# 11_LMS1_Power.net
KiCad netlist of a schematic drawn in Altium Designer
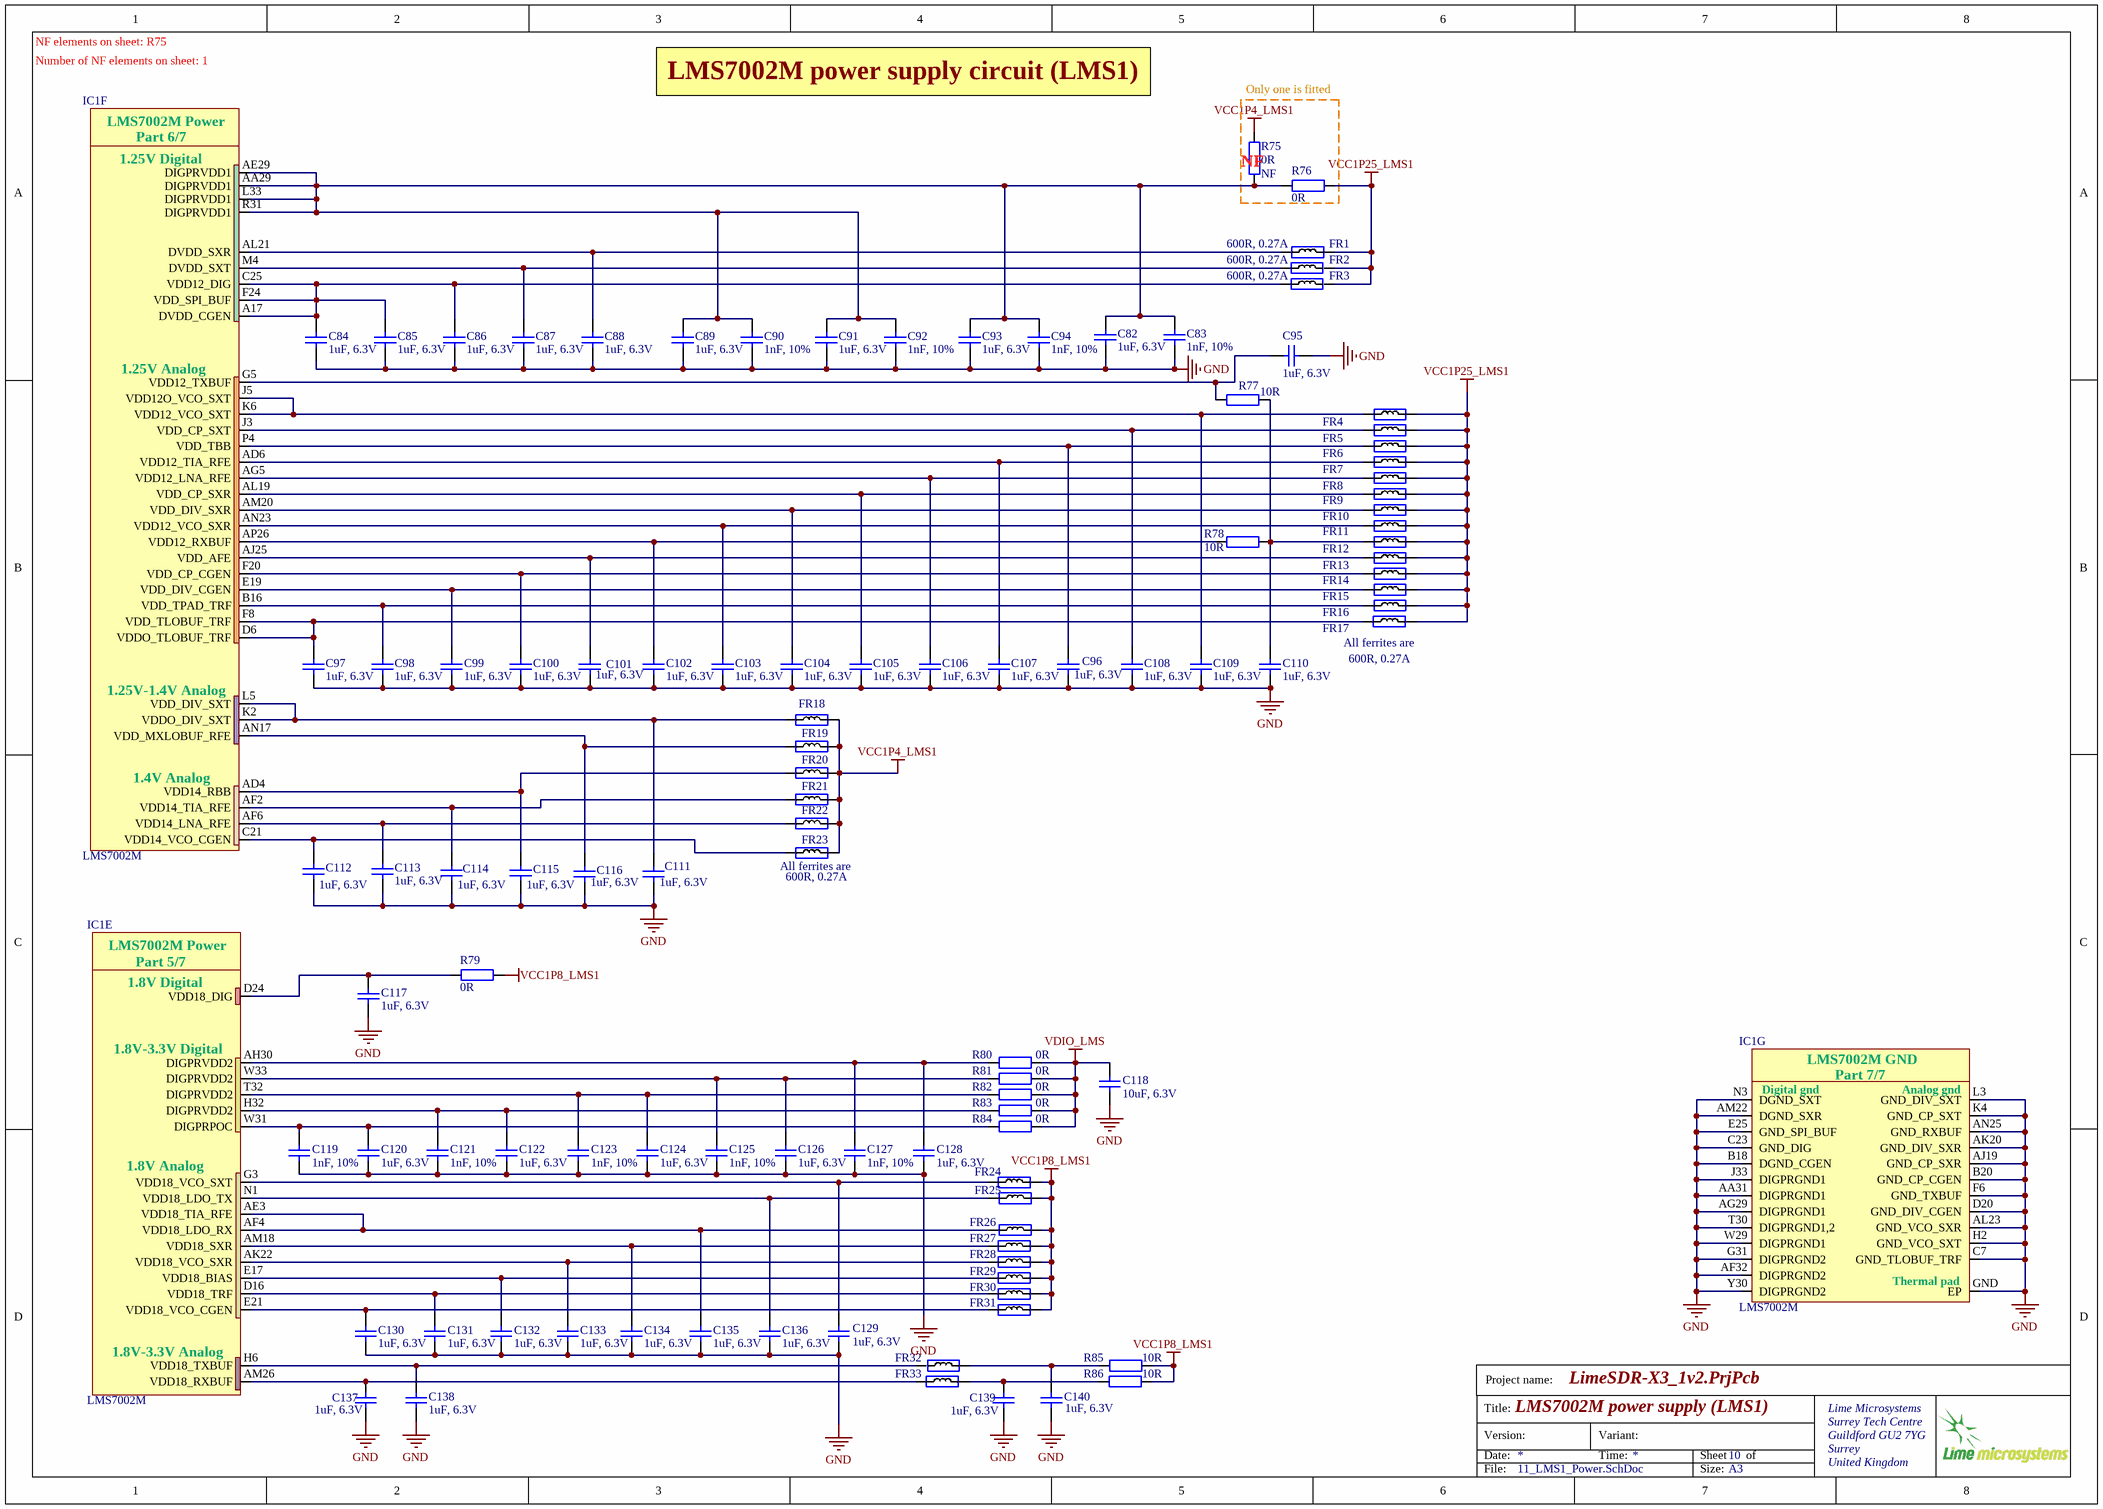
[diagram p0: 11_LMS1_Power.SchDoc]

(export (version "E")
  (design (tool "Eeschema 10.0.6"))
  (components
    (comp (ref "C82")
      (value "1uF, 6.3V")
      (footprint "CAP0201")
      (fields (field (name "TOLERANCE") "±20%") (field (name "MANUFACTURER") "TDK Corporation"))
      (libsource (lib "") (part "Cap_0402_1"))
    )
    (comp (ref "C83")
      (value "1nF, 10%")
      (footprint "CAP0201")
      (fields (field (name "TOLERANCE") "±10%") (field (name "MANUFACTURER") "TDK Corporation"))
      (libsource (lib "") (part "Cap_0402_1"))
    )
    (comp (ref "C84")
      (value "1uF, 6.3V")
      (footprint "CAP0201")
      (fields (field (name "TOLERANCE") "±20%") (field (name "MANUFACTURER") "TDK Corporation"))
      (libsource (lib "") (part "Cap_0402_3"))
    )
    (comp (ref "C85")
      (value "1uF, 6.3V")
      (footprint "CAP0201")
      (fields (field (name "TOLERANCE") "±20%") (field (name "MANUFACTURER") "TDK Corporation"))
      (libsource (lib "") (part "Cap_0402_3"))
    )
    (comp (ref "C86")
      (value "1uF, 6.3V")
      (footprint "CAP0201")
      (fields (field (name "TOLERANCE") "±20%") (field (name "MANUFACTURER") "TDK Corporation"))
      (libsource (lib "") (part "Cap_0402_3"))
    )
    (comp (ref "C87")
      (value "1uF, 6.3V")
      (footprint "CAP0201")
      (fields (field (name "TOLERANCE") "±20%") (field (name "MANUFACTURER") "TDK Corporation"))
      (libsource (lib "") (part "Cap_0402_1"))
    )
    (comp (ref "C88")
      (value "1uF, 6.3V")
      (footprint "CAP0201")
      (fields (field (name "TOLERANCE") "±20%") (field (name "MANUFACTURER") "TDK Corporation"))
      (libsource (lib "") (part "Cap_0402_3"))
    )
    (comp (ref "C89")
      (value "1uF, 6.3V")
      (footprint "CAP0201")
      (fields (field (name "TOLERANCE") "±20%") (field (name "MANUFACTURER") "TDK Corporation"))
      (libsource (lib "") (part "Cap_0402_1"))
    )
    (comp (ref "C90")
      (value "1nF, 10%")
      (footprint "CAP0201")
      (fields (field (name "TOLERANCE") "±10%") (field (name "MANUFACTURER") "TDK Corporation"))
      (libsource (lib "") (part "Cap_0402_1"))
    )
    (comp (ref "C91")
      (value "1uF, 6.3V")
      (footprint "CAP0201")
      (fields (field (name "TOLERANCE") "±20%") (field (name "MANUFACTURER") "TDK Corporation"))
      (libsource (lib "") (part "Cap_0402_1"))
    )
    (comp (ref "C92")
      (value "1nF, 10%")
      (footprint "CAP0201")
      (fields (field (name "TOLERANCE") "±10%") (field (name "MANUFACTURER") "TDK Corporation"))
      (libsource (lib "") (part "Cap_0402_1"))
    )
    (comp (ref "C93")
      (value "1uF, 6.3V")
      (footprint "CAP0201")
      (fields (field (name "TOLERANCE") "±20%") (field (name "MANUFACTURER") "TDK Corporation"))
      (libsource (lib "") (part "Cap_0402_1"))
    )
    (comp (ref "C94")
      (value "1nF, 10%")
      (footprint "CAP0201")
      (fields (field (name "TOLERANCE") "±10%") (field (name "MANUFACTURER") "TDK Corporation"))
      (libsource (lib "") (part "Cap_0402_1"))
    )
    (comp (ref "C95")
      (value "1uF, 6.3V")
      (footprint "CAP0201")
      (fields (field (name "TOLERANCE") "±20%") (field (name "MANUFACTURER") "TDK Corporation"))
      (libsource (lib "") (part "Cap_0402_4"))
    )
    (comp (ref "C96")
      (value "1uF, 6.3V")
      (footprint "CAP0201")
      (fields (field (name "TOLERANCE") "±20%") (field (name "MANUFACTURER") "TDK Corporation"))
      (libsource (lib "") (part "Cap_0402_3"))
    )
    (comp (ref "C97")
      (value "1uF, 6.3V")
      (footprint "CAP0201")
      (fields (field (name "TOLERANCE") "±20%") (field (name "MANUFACTURER") "TDK Corporation"))
      (libsource (lib "") (part "Cap_0402_3"))
    )
    (comp (ref "C98")
      (value "1uF, 6.3V")
      (footprint "CAP0201")
      (fields (field (name "TOLERANCE") "±20%") (field (name "MANUFACTURER") "TDK Corporation"))
      (libsource (lib "") (part "Cap_0402_3"))
    )
    (comp (ref "C99")
      (value "1uF, 6.3V")
      (footprint "CAP0201")
      (fields (field (name "TOLERANCE") "±20%") (field (name "MANUFACTURER") "TDK Corporation"))
      (libsource (lib "") (part "Cap_0402_3"))
    )
    (comp (ref "C100")
      (value "1uF, 6.3V")
      (footprint "CAP0201")
      (fields (field (name "TOLERANCE") "±20%") (field (name "MANUFACTURER") "TDK Corporation"))
      (libsource (lib "") (part "Cap_0402_1"))
    )
    (comp (ref "C101")
      (value "1uF, 6.3V")
      (footprint "CAP0201")
      (fields (field (name "TOLERANCE") "±20%") (field (name "MANUFACTURER") "TDK Corporation"))
      (libsource (lib "") (part "Cap_0402_3"))
    )
    (comp (ref "C102")
      (value "1uF, 6.3V")
      (footprint "CAP0201")
      (fields (field (name "TOLERANCE") "±20%") (field (name "MANUFACTURER") "TDK Corporation"))
      (libsource (lib "") (part "Cap_0402_3"))
    )
    (comp (ref "C103")
      (value "1uF, 6.3V")
      (footprint "CAP0201")
      (fields (field (name "TOLERANCE") "±20%") (field (name "MANUFACTURER") "TDK Corporation"))
      (libsource (lib "") (part "Cap_0402_3"))
    )
    (comp (ref "C104")
      (value "1uF, 6.3V")
      (footprint "CAP0201")
      (fields (field (name "TOLERANCE") "±20%") (field (name "MANUFACTURER") "TDK Corporation"))
      (libsource (lib "") (part "Cap_0402_3"))
    )
    (comp (ref "C105")
      (value "1uF, 6.3V")
      (footprint "CAP0201")
      (fields (field (name "TOLERANCE") "±20%") (field (name "MANUFACTURER") "TDK Corporation"))
      (libsource (lib "") (part "Cap_0402_3"))
    )
    (comp (ref "C106")
      (value "1uF, 6.3V")
      (footprint "CAP0201")
      (fields (field (name "TOLERANCE") "±20%") (field (name "MANUFACTURER") "TDK Corporation"))
      (libsource (lib "") (part "Cap_0402_3"))
    )
    (comp (ref "C107")
      (value "1uF, 6.3V")
      (footprint "CAP0201")
      (fields (field (name "TOLERANCE") "±20%") (field (name "MANUFACTURER") "TDK Corporation"))
      (libsource (lib "") (part "Cap_0402_1"))
    )
    (comp (ref "C108")
      (value "1uF, 6.3V")
      (footprint "CAP0201")
      (fields (field (name "TOLERANCE") "±20%") (field (name "MANUFACTURER") "TDK Corporation"))
      (libsource (lib "") (part "Cap_0402_3"))
    )
    (comp (ref "C109")
      (value "1uF, 6.3V")
      (footprint "CAP0201")
      (fields (field (name "TOLERANCE") "±20%") (field (name "MANUFACTURER") "TDK Corporation"))
      (libsource (lib "") (part "Cap_0402_1"))
    )
    (comp (ref "C110")
      (value "1uF, 6.3V")
      (footprint "CAP0201")
      (fields (field (name "TOLERANCE") "±20%") (field (name "MANUFACTURER") "TDK Corporation"))
      (libsource (lib "") (part "Cap_0402_1"))
    )
    (comp (ref "C111")
      (value "1uF, 6.3V")
      (footprint "CAP0201")
      (fields (field (name "TOLERANCE") "±20%") (field (name "MANUFACTURER") "TDK Corporation"))
      (libsource (lib "") (part "Cap_0402_3"))
    )
    (comp (ref "C112")
      (value "1uF, 6.3V")
      (footprint "CAP0201")
      (fields (field (name "TOLERANCE") "±20%") (field (name "MANUFACTURER") "TDK Corporation"))
      (libsource (lib "") (part "Cap_0402_3"))
    )
    (comp (ref "C113")
      (value "1uF, 6.3V")
      (footprint "CAP0201")
      (fields (field (name "TOLERANCE") "±20%") (field (name "MANUFACTURER") "TDK Corporation"))
      (libsource (lib "") (part "Cap_0402_3"))
    )
    (comp (ref "C114")
      (value "1uF, 6.3V")
      (footprint "CAP0201")
      (fields (field (name "TOLERANCE") "±20%") (field (name "MANUFACTURER") "TDK Corporation"))
      (libsource (lib "LimeMicroAltiumLib_schLib") (part "Cap_0402"))
    )
    (comp (ref "C115")
      (value "1uF, 6.3V")
      (footprint "CAP0201")
      (fields (field (name "TOLERANCE") "±20%") (field (name "MANUFACTURER") "TDK Corporation"))
      (libsource (lib "LimeMicroAltiumLib_schLib") (part "Cap_0402"))
    )
    (comp (ref "C116")
      (value "1uF, 6.3V")
      (footprint "CAP0201")
      (fields (field (name "TOLERANCE") "±20%") (field (name "MANUFACTURER") "TDK Corporation"))
      (libsource (lib "") (part "Cap_0402_3"))
    )
    (comp (ref "C117")
      (value "1uF, 6.3V")
      (footprint "CAP0201")
      (fields (field (name "TOLERANCE") "±20%") (field (name "MANUFACTURER") "TDK Corporation"))
      (libsource (lib "") (part "Cap_0402_2"))
    )
    (comp (ref "C118")
      (value "10uF, 6.3V")
      (footprint "CAP0603")
      (fields (field (name "TOLERANCE") "±20%") (field (name "MANUFACTURER") "Yageo"))
      (libsource (lib "LimeFPGAboard_schLib") (part "Cap_0603"))
    )
    (comp (ref "C119")
      (value "1nF, 10%")
      (footprint "CAP0201")
      (fields (field (name "TOLERANCE") "±10%") (field (name "MANUFACTURER") "TDK Corporation"))
      (libsource (lib "") (part "Cap_0402_2"))
    )
    (comp (ref "C120")
      (value "1uF, 6.3V")
      (footprint "CAP0201")
      (fields (field (name "TOLERANCE") "±20%") (field (name "MANUFACTURER") "TDK Corporation"))
      (libsource (lib "") (part "Cap_0402_2"))
    )
    (comp (ref "C121")
      (value "1nF, 10%")
      (footprint "CAP0201")
      (fields (field (name "TOLERANCE") "±10%") (field (name "MANUFACTURER") "TDK Corporation"))
      (libsource (lib "") (part "Cap_0402_2"))
    )
    (comp (ref "C122")
      (value "1uF, 6.3V")
      (footprint "CAP0201")
      (fields (field (name "TOLERANCE") "±20%") (field (name "MANUFACTURER") "TDK Corporation"))
      (libsource (lib "") (part "Cap_0402_2"))
    )
    (comp (ref "C123")
      (value "1nF, 10%")
      (footprint "CAP0201")
      (fields (field (name "TOLERANCE") "±10%") (field (name "MANUFACTURER") "TDK Corporation"))
      (libsource (lib "") (part "Cap_0402_2"))
    )
    (comp (ref "C124")
      (value "1uF, 6.3V")
      (footprint "CAP0201")
      (fields (field (name "TOLERANCE") "±20%") (field (name "MANUFACTURER") "TDK Corporation"))
      (libsource (lib "") (part "Cap_0402_2"))
    )
    (comp (ref "C125")
      (value "1nF, 10%")
      (footprint "CAP0201")
      (fields (field (name "TOLERANCE") "±10%") (field (name "MANUFACTURER") "TDK Corporation"))
      (libsource (lib "") (part "Cap_0402_2"))
    )
    (comp (ref "C126")
      (value "1uF, 6.3V")
      (footprint "CAP0201")
      (fields (field (name "TOLERANCE") "±20%") (field (name "MANUFACTURER") "TDK Corporation"))
      (libsource (lib "") (part "Cap_0402_2"))
    )
    (comp (ref "C127")
      (value "1nF, 10%")
      (footprint "CAP0201")
      (fields (field (name "TOLERANCE") "±10%") (field (name "MANUFACTURER") "TDK Corporation"))
      (libsource (lib "") (part "Cap_0402_2"))
    )
    (comp (ref "C128")
      (value "1uF, 6.3V")
      (footprint "CAP0201")
      (fields (field (name "TOLERANCE") "±20%") (field (name "MANUFACTURER") "TDK Corporation"))
      (libsource (lib "") (part "Cap_0402_2"))
    )
    (comp (ref "C129")
      (value "1uF, 6.3V")
      (footprint "CAP0201")
      (fields (field (name "TOLERANCE") "±20%") (field (name "MANUFACTURER") "TDK Corporation"))
      (libsource (lib "") (part "Cap_0402_2"))
    )
    (comp (ref "C130")
      (value "1uF, 6.3V")
      (footprint "CAP0201")
      (fields (field (name "TOLERANCE") "±20%") (field (name "MANUFACTURER") "TDK Corporation"))
      (libsource (lib "") (part "Cap_0402_2"))
    )
    (comp (ref "C131")
      (value "1uF, 6.3V")
      (footprint "CAP0201")
      (fields (field (name "TOLERANCE") "±20%") (field (name "MANUFACTURER") "TDK Corporation"))
      (libsource (lib "") (part "Cap_0402_2"))
    )
    (comp (ref "C132")
      (value "1uF, 6.3V")
      (footprint "CAP0201")
      (fields (field (name "TOLERANCE") "±20%") (field (name "MANUFACTURER") "TDK Corporation"))
      (libsource (lib "") (part "Cap_0402_2"))
    )
    (comp (ref "C133")
      (value "1uF, 6.3V")
      (footprint "CAP0201")
      (fields (field (name "TOLERANCE") "±20%") (field (name "MANUFACTURER") "TDK Corporation"))
      (libsource (lib "") (part "Cap_0402_2"))
    )
    (comp (ref "C134")
      (value "1uF, 6.3V")
      (footprint "CAP0201")
      (fields (field (name "TOLERANCE") "±20%") (field (name "MANUFACTURER") "TDK Corporation"))
      (libsource (lib "") (part "Cap_0402_2"))
    )
    (comp (ref "C135")
      (value "1uF, 6.3V")
      (footprint "CAP0201")
      (fields (field (name "TOLERANCE") "±20%") (field (name "MANUFACTURER") "TDK Corporation"))
      (libsource (lib "") (part "Cap_0402_2"))
    )
    (comp (ref "C136")
      (value "1uF, 6.3V")
      (footprint "CAP0201")
      (fields (field (name "TOLERANCE") "±20%") (field (name "MANUFACTURER") "TDK Corporation"))
      (libsource (lib "") (part "Cap_0402_2"))
    )
    (comp (ref "C137")
      (value "1uF, 6.3V")
      (footprint "CAP0201")
      (fields (field (name "TOLERANCE") "±20%") (field (name "MANUFACTURER") "TDK Corporation"))
      (libsource (lib "") (part "Cap_0402_2"))
    )
    (comp (ref "C138")
      (value "1uF, 6.3V")
      (footprint "CAP0201")
      (fields (field (name "TOLERANCE") "±20%") (field (name "MANUFACTURER") "TDK Corporation"))
      (libsource (lib "") (part "Cap_0402_2"))
    )
    (comp (ref "C139")
      (value "1uF, 6.3V")
      (footprint "CAP0201")
      (fields (field (name "TOLERANCE") "±20%") (field (name "MANUFACTURER") "TDK Corporation"))
      (libsource (lib "") (part "Cap_0402_2"))
    )
    (comp (ref "C140")
      (value "1uF, 6.3V")
      (footprint "CAP0201")
      (fields (field (name "TOLERANCE") "±20%") (field (name "MANUFACTURER") "TDK Corporation"))
      (libsource (lib "") (part "Cap_0402_2"))
    )
    (comp (ref "FR1")
      (value "600R, 0.27A")
      (footprint "RES0201")
      (fields (field (name "MANUFACTURER") "Taiyo Yuden"))
      (libsource (lib "") (part "Ferrite_2"))
    )
    (comp (ref "FR2")
      (value "600R, 0.27A")
      (footprint "RES0201")
      (fields (field (name "MANUFACTURER") "Taiyo Yuden"))
      (libsource (lib "LimeMicroAltiumLib_schLib") (part "Ferrite"))
    )
    (comp (ref "FR3")
      (value "600R, 0.27A")
      (footprint "RES0201")
      (fields (field (name "MANUFACTURER") "Taiyo Yuden"))
      (libsource (lib "LimeMicroAltiumLib_schLib") (part "Ferrite"))
    )
    (comp (ref "FR4")
      (value "600R, 0.27A")
      (footprint "RES0201")
      (fields (field (name "MANUFACTURER") "Taiyo Yuden"))
      (libsource (lib "") (part "Ferrite_2"))
    )
    (comp (ref "FR5")
      (value "600R, 0.27A")
      (footprint "RES0201")
      (fields (field (name "MANUFACTURER") "Taiyo Yuden"))
      (libsource (lib "") (part "Ferrite_2"))
    )
    (comp (ref "FR6")
      (value "600R, 0.27A")
      (footprint "RES0201")
      (fields (field (name "MANUFACTURER") "Taiyo Yuden"))
      (libsource (lib "") (part "Ferrite_2"))
    )
    (comp (ref "FR7")
      (value "600R, 0.27A")
      (footprint "RES0201")
      (fields (field (name "MANUFACTURER") "Taiyo Yuden"))
      (libsource (lib "") (part "Ferrite_2"))
    )
    (comp (ref "FR8")
      (value "600R, 0.27A")
      (footprint "RES0201")
      (fields (field (name "MANUFACTURER") "Taiyo Yuden"))
      (libsource (lib "") (part "Ferrite_2"))
    )
    (comp (ref "FR9")
      (value "600R, 0.27A")
      (footprint "RES0201")
      (fields (field (name "MANUFACTURER") "Taiyo Yuden"))
      (libsource (lib "") (part "Ferrite_2"))
    )
    (comp (ref "FR10")
      (value "600R, 0.27A")
      (footprint "RES0201")
      (fields (field (name "MANUFACTURER") "Taiyo Yuden"))
      (libsource (lib "") (part "Ferrite_2"))
    )
    (comp (ref "FR11")
      (value "600R, 0.27A")
      (footprint "RES0201")
      (fields (field (name "MANUFACTURER") "Taiyo Yuden"))
      (libsource (lib "") (part "Ferrite_2"))
    )
    (comp (ref "FR12")
      (value "600R, 0.27A")
      (footprint "RES0201")
      (fields (field (name "MANUFACTURER") "Taiyo Yuden"))
      (libsource (lib "") (part "Ferrite_2"))
    )
    (comp (ref "FR13")
      (value "600R, 0.27A")
      (footprint "RES0201")
      (fields (field (name "MANUFACTURER") "Taiyo Yuden"))
      (libsource (lib "") (part "Ferrite_2"))
    )
    (comp (ref "FR14")
      (value "600R, 0.27A")
      (footprint "RES0201")
      (fields (field (name "MANUFACTURER") "Taiyo Yuden"))
      (libsource (lib "") (part "Ferrite_2"))
    )
    (comp (ref "FR15")
      (value "600R, 0.27A")
      (footprint "RES0201")
      (fields (field (name "MANUFACTURER") "Taiyo Yuden"))
      (libsource (lib "") (part "Ferrite_2"))
    )
    (comp (ref "FR16")
      (value "600R, 0.27A")
      (footprint "RES0201")
      (fields (field (name "MANUFACTURER") "Taiyo Yuden"))
      (libsource (lib "") (part "Ferrite_2"))
    )
    (comp (ref "FR17")
      (value "600R, 0.27A")
      (footprint "RES0201")
      (fields (field (name "MANUFACTURER") "Taiyo Yuden"))
      (libsource (lib "LimeMicroAltiumLib_schLib") (part "Ferrite"))
    )
    (comp (ref "FR18")
      (value "600R, 0.27A")
      (footprint "RES0201")
      (fields (field (name "MANUFACTURER") "Taiyo Yuden"))
      (libsource (lib "LimeMicroAltiumLib_schLib") (part "Ferrite"))
    )
    (comp (ref "FR19")
      (value "600R, 0.27A")
      (footprint "RES0201")
      (fields (field (name "MANUFACTURER") "Taiyo Yuden"))
      (libsource (lib "LimeMicroAltiumLib_schLib") (part "Ferrite"))
    )
    (comp (ref "FR20")
      (value "600R, 0.27A")
      (footprint "RES0201")
      (fields (field (name "MANUFACTURER") "Taiyo Yuden"))
      (libsource (lib "LimeMicroAltiumLib_schLib") (part "Ferrite"))
    )
    (comp (ref "FR21")
      (value "600R, 0.27A")
      (footprint "RES0201")
      (fields (field (name "MANUFACTURER") "Taiyo Yuden"))
      (libsource (lib "LimeMicroAltiumLib_schLib") (part "Ferrite"))
    )
    (comp (ref "FR22")
      (value "600R, 0.27A")
      (footprint "RES0201")
      (fields (field (name "MANUFACTURER") "Taiyo Yuden"))
      (libsource (lib "LimeMicroAltiumLib_schLib") (part "Ferrite"))
    )
    (comp (ref "FR23")
      (value "600R, 0.27A")
      (footprint "RES0201")
      (fields (field (name "MANUFACTURER") "Taiyo Yuden"))
      (libsource (lib "LimeMicroAltiumLib_schLib") (part "Ferrite"))
    )
    (comp (ref "FR24")
      (value "600R, 0.27A")
      (footprint "RES0201")
      (fields (field (name "MANUFACTURER") "Taiyo Yuden"))
      (libsource (lib "LimeMicroAltiumLib_schLib") (part "Ferrite"))
    )
    (comp (ref "FR25")
      (value "600R, 0.27A")
      (footprint "RES0201")
      (fields (field (name "MANUFACTURER") "Taiyo Yuden"))
      (libsource (lib "") (part "Ferrite_1"))
    )
    (comp (ref "FR26")
      (value "600R, 0.27A")
      (footprint "RES0201")
      (fields (field (name "MANUFACTURER") "Taiyo Yuden"))
      (libsource (lib "") (part "Ferrite_1"))
    )
    (comp (ref "FR27")
      (value "600R, 0.27A")
      (footprint "RES0201")
      (fields (field (name "MANUFACTURER") "Taiyo Yuden"))
      (libsource (lib "LimeMicroAltiumLib_schLib") (part "Ferrite"))
    )
    (comp (ref "FR28")
      (value "600R, 0.27A")
      (footprint "RES0201")
      (fields (field (name "MANUFACTURER") "Taiyo Yuden"))
      (libsource (lib "LimeMicroAltiumLib_schLib") (part "Ferrite"))
    )
    (comp (ref "FR29")
      (value "600R, 0.27A")
      (footprint "RES0201")
      (fields (field (name "MANUFACTURER") "Taiyo Yuden"))
      (libsource (lib "LimeMicroAltiumLib_schLib") (part "Ferrite"))
    )
    (comp (ref "FR30")
      (value "600R, 0.27A")
      (footprint "RES0201")
      (fields (field (name "MANUFACTURER") "Taiyo Yuden"))
      (libsource (lib "LimeMicroAltiumLib_schLib") (part "Ferrite"))
    )
    (comp (ref "FR31")
      (value "600R, 0.27A")
      (footprint "RES0201")
      (fields (field (name "MANUFACTURER") "Taiyo Yuden"))
      (libsource (lib "LimeMicroAltiumLib_schLib") (part "Ferrite"))
    )
    (comp (ref "FR32")
      (value "600R, 0.27A")
      (footprint "RES0201")
      (fields (field (name "MANUFACTURER") "Taiyo Yuden"))
      (libsource (lib "") (part "Ferrite_1"))
    )
    (comp (ref "FR33")
      (value "600R, 0.27A")
      (footprint "RES0201")
      (fields (field (name "MANUFACTURER") "Taiyo Yuden"))
      (libsource (lib "LimeMicroAltiumLib_schLib") (part "Ferrite"))
    )
    (comp (ref "IC1")
      (value "LMS7002M")
      (footprint "LMS7002M_v5")
      (description "Schematic symbol revision 4. Default footprint - 0.31mm pad")
      (fields (field (name "MANUFACTURER") "Lime Microsystems"))
      (libsource (lib "LimeMicroAltiumLib_schLib_r04") (part "LMS7002Mr4"))
    )
    (comp (ref "R75")
      (value "0R")
      (footprint "RES0402")
      (fields
        (field (name "ASSEMBLY INFO") "NF")
        (field (name "MANUFACTURER") "Yageo")
        (field (name "TOLERANCE") "Jumper")
      )
      (libsource (lib "LimeMicroAltiumLib_schLib") (part "Res_0402"))
    )
    (comp (ref "R76")
      (value "0R")
      (footprint "RES0402")
      (fields (field (name "MANUFACTURER") "Yageo") (field (name "TOLERANCE") "Jumper"))
      (libsource (lib "") (part "Res_0402_1"))
    )
    (comp (ref "R77")
      (value "10R")
      (footprint "RES0201")
      (fields
        (field (name "MANUFACTURER") "Panasonic Electronic Components")
        (field (name "TOLERANCE") "±1%")
      )
      (libsource (lib "LimeMicroAltiumLib_schLib") (part "Res_0402"))
    )
    (comp (ref "R78")
      (value "10R")
      (footprint "RES0201")
      (fields
        (field (name "MANUFACTURER") "Panasonic Electronic Components")
        (field (name "TOLERANCE") "±1%")
      )
      (libsource (lib "LimeMicroAltiumLib_schLib") (part "Res_0402"))
    )
    (comp (ref "R79")
      (value "0R")
      (footprint "RES0201")
      (fields (field (name "MANUFACTURER") "Rohm Semiconductor") (field (name "TOLERANCE") "Jumper"))
      (libsource (lib "LimeMicroAltiumLib_schLib") (part "Res_0402"))
    )
    (comp (ref "R80")
      (value "0R")
      (footprint "RES0402")
      (fields (field (name "MANUFACTURER") "Yageo") (field (name "TOLERANCE") "Jumper"))
      (libsource (lib "LimeMicroAltiumLib_schLib") (part "Res_0402"))
    )
    (comp (ref "R81")
      (value "0R")
      (footprint "RES0402")
      (fields (field (name "MANUFACTURER") "Yageo") (field (name "TOLERANCE") "Jumper"))
      (libsource (lib "LimeMicroAltiumLib_schLib") (part "Res_0402"))
    )
    (comp (ref "R82")
      (value "0R")
      (footprint "RES0402")
      (fields (field (name "MANUFACTURER") "Yageo") (field (name "TOLERANCE") "Jumper"))
      (libsource (lib "LimeMicroAltiumLib_schLib") (part "Res_0402"))
    )
    (comp (ref "R83")
      (value "0R")
      (footprint "RES0402")
      (fields (field (name "MANUFACTURER") "Yageo") (field (name "TOLERANCE") "Jumper"))
      (libsource (lib "LimeMicroAltiumLib_schLib") (part "Res_0402"))
    )
    (comp (ref "R84")
      (value "0R")
      (footprint "RES0402")
      (fields (field (name "MANUFACTURER") "Yageo") (field (name "TOLERANCE") "Jumper"))
      (libsource (lib "LimeMicroAltiumLib_schLib") (part "Res_0402"))
    )
    (comp (ref "R85")
      (value "10R")
      (footprint "RES0201")
      (fields
        (field (name "MANUFACTURER") "Panasonic Electronic Components")
        (field (name "TOLERANCE") "±1%")
      )
      (libsource (lib "LimeMicroAltiumLib_schLib") (part "Res_0402"))
    )
    (comp (ref "R86")
      (value "10R")
      (footprint "RES0201")
      (fields
        (field (name "MANUFACTURER") "Panasonic Electronic Components")
        (field (name "TOLERANCE") "±1%")
      )
      (libsource (lib "LimeMicroAltiumLib_schLib") (part "Res_0402"))
    )
  )
  (nets
    (net (code "1") (name "GND") (class "Default")
      (node (ref "C100") (pin "1") (pinfunction "1_1") (pintype "passive"))
      (node (ref "C101") (pin "2") (pinfunction "2_2") (pintype "passive"))
      (node (ref "C102") (pin "2") (pinfunction "2_2") (pintype "passive"))
      (node (ref "C103") (pin "2") (pinfunction "2_2") (pintype "passive"))
      (node (ref "C104") (pin "2") (pinfunction "2_2") (pintype "passive"))
      (node (ref "C105") (pin "2") (pinfunction "2_2") (pintype "passive"))
      (node (ref "C106") (pin "2") (pinfunction "2_2") (pintype "passive"))
      (node (ref "C107") (pin "1") (pinfunction "1_1") (pintype "passive"))
      (node (ref "C108") (pin "2") (pinfunction "2_2") (pintype "passive"))
      (node (ref "C109") (pin "1") (pinfunction "1_1") (pintype "passive"))
      (node (ref "C110") (pin "1") (pinfunction "1_1") (pintype "passive"))
      (node (ref "C111") (pin "2") (pinfunction "2_2") (pintype "passive"))
      (node (ref "C112") (pin "2") (pinfunction "2_2") (pintype "passive"))
      (node (ref "C113") (pin "2") (pinfunction "2_2") (pintype "passive"))
      (node (ref "C114") (pin "2") (pinfunction "2_2") (pintype "passive"))
      (node (ref "C115") (pin "2") (pinfunction "2_2") (pintype "passive"))
      (node (ref "C116") (pin "2") (pinfunction "2_2") (pintype "passive"))
      (node (ref "C117") (pin "2") (pinfunction "2_2") (pintype "passive"))
      (node (ref "C118") (pin "1") (pinfunction "1_1") (pintype "passive"))
      (node (ref "C119") (pin "2") (pinfunction "2_2") (pintype "passive"))
      (node (ref "C120") (pin "2") (pinfunction "2_2") (pintype "passive"))
      (node (ref "C121") (pin "2") (pinfunction "2_2") (pintype "passive"))
      (node (ref "C122") (pin "2") (pinfunction "2_2") (pintype "passive"))
      (node (ref "C123") (pin "2") (pinfunction "2_2") (pintype "passive"))
      (node (ref "C124") (pin "2") (pinfunction "2_2") (pintype "passive"))
      (node (ref "C125") (pin "2") (pinfunction "2_2") (pintype "passive"))
      (node (ref "C126") (pin "2") (pinfunction "2_2") (pintype "passive"))
      (node (ref "C127") (pin "2") (pinfunction "2_2") (pintype "passive"))
      (node (ref "C128") (pin "2") (pinfunction "2_2") (pintype "passive"))
      (node (ref "C129") (pin "2") (pinfunction "2_2") (pintype "passive"))
      (node (ref "C130") (pin "2") (pinfunction "2_2") (pintype "passive"))
      (node (ref "C131") (pin "2") (pinfunction "2_2") (pintype "passive"))
      (node (ref "C132") (pin "2") (pinfunction "2_2") (pintype "passive"))
      (node (ref "C133") (pin "2") (pinfunction "2_2") (pintype "passive"))
      (node (ref "C134") (pin "2") (pinfunction "2_2") (pintype "passive"))
      (node (ref "C135") (pin "2") (pinfunction "2_2") (pintype "passive"))
      (node (ref "C136") (pin "2") (pinfunction "2_2") (pintype "passive"))
      (node (ref "C137") (pin "2") (pinfunction "2_2") (pintype "passive"))
      (node (ref "C138") (pin "2") (pinfunction "2_2") (pintype "passive"))
      (node (ref "C139") (pin "2") (pinfunction "2_2") (pintype "passive"))
      (node (ref "C140") (pin "2") (pinfunction "2_2") (pintype "passive"))
      (node (ref "C82") (pin "2") (pinfunction "2_2") (pintype "passive"))
      (node (ref "C83") (pin "2") (pinfunction "2_2") (pintype "passive"))
      (node (ref "C84") (pin "2") (pinfunction "2_2") (pintype "passive"))
      (node (ref "C85") (pin "2") (pinfunction "2_2") (pintype "passive"))
      (node (ref "C86") (pin "2") (pinfunction "2_2") (pintype "passive"))
      (node (ref "C87") (pin "1") (pinfunction "1_1") (pintype "passive"))
      (node (ref "C88") (pin "2") (pinfunction "2_2") (pintype "passive"))
      (node (ref "C89") (pin "2") (pinfunction "2_2") (pintype "passive"))
      (node (ref "C90") (pin "2") (pinfunction "2_2") (pintype "passive"))
      (node (ref "C91") (pin "2") (pinfunction "2_2") (pintype "passive"))
      (node (ref "C92") (pin "2") (pinfunction "2_2") (pintype "passive"))
      (node (ref "C93") (pin "2") (pinfunction "2_2") (pintype "passive"))
      (node (ref "C94") (pin "2") (pinfunction "2_2") (pintype "passive"))
      (node (ref "C95") (pin "2") (pinfunction "2_2") (pintype "passive"))
      (node (ref "C96") (pin "2") (pinfunction "2_2") (pintype "passive"))
      (node (ref "C97") (pin "2") (pinfunction "2_2") (pintype "passive"))
      (node (ref "C98") (pin "2") (pinfunction "2_2") (pintype "passive"))
      (node (ref "C99") (pin "2") (pinfunction "2_2") (pintype "passive"))
      (node (ref "IC1") (pin "AA31") (pinfunction "DIGPRGND1_AA31") (pintype "passive"))
      (node (ref "IC1") (pin "AF32") (pinfunction "DIGPRGND2_AF32") (pintype "passive"))
      (node (ref "IC1") (pin "AG29") (pinfunction "DIGPRGND1_AG29") (pintype "passive"))
      (node (ref "IC1") (pin "AJ19") (pinfunction "GND_CP_SXR_AJ19") (pintype "passive"))
      (node (ref "IC1") (pin "AK20") (pinfunction "GND_DIV_SXR_AK20") (pintype "passive"))
      (node (ref "IC1") (pin "AL23") (pinfunction "GND_VCO_SXR_AL23") (pintype "passive"))
      (node (ref "IC1") (pin "AM22") (pinfunction "DGND_SXR_AM22") (pintype "passive"))
      (node (ref "IC1") (pin "AN25") (pinfunction "GND_RXBUF_AN25") (pintype "passive"))
      (node (ref "IC1") (pin "B18") (pinfunction "DGND_CGEN_B18") (pintype "passive"))
      (node (ref "IC1") (pin "B20") (pinfunction "GND_CP_CGEN_B20") (pintype "passive"))
      (node (ref "IC1") (pin "C23") (pinfunction "GND_DIG_C23") (pintype "passive"))
      (node (ref "IC1") (pin "C7") (pinfunction "GND_TLOBUF_TRF_C7") (pintype "passive"))
      (node (ref "IC1") (pin "D20") (pinfunction "GND_DIV_CGEN_D20") (pintype "passive"))
      (node (ref "IC1") (pin "E25") (pinfunction "GND_SPI_BUF_E25") (pintype "passive"))
      (node (ref "IC1") (pin "F6") (pinfunction "GND_TXBUF_F6") (pintype "passive"))
      (node (ref "IC1") (pin "G31") (pinfunction "DIGPRGND2_G31") (pintype "passive"))
      (node (ref "IC1") (pin "GND") (pinfunction "EP_GND") (pintype "passive"))
      (node (ref "IC1") (pin "H2") (pinfunction "GND_VCO_SXT_H2") (pintype "passive"))
      (node (ref "IC1") (pin "J33") (pinfunction "DIGPRGND1_J33") (pintype "passive"))
      (node (ref "IC1") (pin "K4") (pinfunction "GND_CP_SXT_K4") (pintype "passive"))
      (node (ref "IC1") (pin "L3") (pinfunction "GND_DIV_SXT_L3") (pintype "passive"))
      (node (ref "IC1") (pin "N3") (pinfunction "DGND_SXT_N3") (pintype "passive"))
      (node (ref "IC1") (pin "T30") (pinfunction "DIGPRGND1,2_T30") (pintype "passive"))
      (node (ref "IC1") (pin "W29") (pinfunction "DIGPRGND1_W29") (pintype "passive"))
      (node (ref "IC1") (pin "Y30") (pinfunction "DIGPRGND2_Y30") (pintype "passive"))
    )
    (net (code "2") (name "Net-(C82-Pad1)") (class "Default")
      (node (ref "C82") (pin "1") (pinfunction "1_1") (pintype "passive"))
      (node (ref "C83") (pin "1") (pinfunction "1_1") (pintype "passive"))
      (node (ref "C89") (pin "1") (pinfunction "1_1") (pintype "passive"))
      (node (ref "C90") (pin "1") (pinfunction "1_1") (pintype "passive"))
      (node (ref "C91") (pin "1") (pinfunction "1_1") (pintype "passive"))
      (node (ref "C92") (pin "1") (pinfunction "1_1") (pintype "passive"))
      (node (ref "C93") (pin "1") (pinfunction "1_1") (pintype "passive"))
      (node (ref "C94") (pin "1") (pinfunction "1_1") (pintype "passive"))
      (node (ref "IC1") (pin "AA29") (pinfunction "DIGPRVDD1_AA29") (pintype "power_in"))
      (node (ref "IC1") (pin "AE29") (pinfunction "DIGPRVDD1_AE29") (pintype "power_in"))
      (node (ref "IC1") (pin "L33") (pinfunction "DIGPRVDD1_L33") (pintype "power_in"))
      (node (ref "IC1") (pin "R31") (pinfunction "DIGPRVDD1_R31") (pintype "power_in"))
      (node (ref "R75") (pin "2") (pinfunction "2_2") (pintype "passive"))
      (node (ref "R76") (pin "2") (pinfunction "2_2") (pintype "passive"))
    )
    (net (code "3") (name "Net-(C110-Pad2)") (class "Default")
      (node (ref "C110") (pin "2") (pinfunction "2_2") (pintype "passive"))
      (node (ref "FR12") (pin "1") (pinfunction "1_1") (pintype "passive"))
      (node (ref "R77") (pin "2") (pinfunction "2_2") (pintype "passive"))
      (node (ref "R78") (pin "2") (pinfunction "2_2") (pintype "passive"))
    )
    (net (code "4") (name "Net-(C121-Pad1)") (class "Default")
      (node (ref "C121") (pin "1") (pinfunction "1_1") (pintype "passive"))
      (node (ref "C122") (pin "1") (pinfunction "1_1") (pintype "passive"))
      (node (ref "IC1") (pin "H32") (pinfunction "DIGPRVDD2_H32") (pintype "power_in"))
      (node (ref "R83") (pin "2") (pinfunction "2_2") (pintype "passive"))
    )
    (net (code "5") (name "Net-(C123-Pad1)") (class "Default")
      (node (ref "C123") (pin "1") (pinfunction "1_1") (pintype "passive"))
      (node (ref "C124") (pin "1") (pinfunction "1_1") (pintype "passive"))
      (node (ref "IC1") (pin "T32") (pinfunction "DIGPRVDD2_T32") (pintype "power_in"))
      (node (ref "R82") (pin "2") (pinfunction "2_2") (pintype "passive"))
    )
    (net (code "6") (name "Net-(C125-Pad1)") (class "Default")
      (node (ref "C125") (pin "1") (pinfunction "1_1") (pintype "passive"))
      (node (ref "C126") (pin "1") (pinfunction "1_1") (pintype "passive"))
      (node (ref "IC1") (pin "W33") (pinfunction "DIGPRVDD2_W33") (pintype "power_in"))
      (node (ref "R81") (pin "2") (pinfunction "2_2") (pintype "passive"))
    )
    (net (code "7") (name "Net-(C127-Pad1)") (class "Default")
      (node (ref "C127") (pin "1") (pinfunction "1_1") (pintype "passive"))
      (node (ref "C128") (pin "1") (pinfunction "1_1") (pintype "passive"))
      (node (ref "IC1") (pin "AH30") (pinfunction "DIGPRVDD2_AH30") (pintype "power_in"))
      (node (ref "R80") (pin "2") (pinfunction "2_2") (pintype "passive"))
    )
    (net (code "8") (name "Net-(C139-Pad1)") (class "Default")
      (node (ref "C139") (pin "1") (pinfunction "1_1") (pintype "passive"))
      (node (ref "FR33") (pin "2") (pinfunction "2_2") (pintype "passive"))
      (node (ref "R86") (pin "2") (pinfunction "2_2") (pintype "passive"))
    )
    (net (code "9") (name "Net-(C140-Pad1)") (class "Default")
      (node (ref "C140") (pin "1") (pinfunction "1_1") (pintype "passive"))
      (node (ref "FR32") (pin "1") (pinfunction "1_1") (pintype "passive"))
      (node (ref "R85") (pin "1") (pinfunction "1_1") (pintype "passive"))
    )
    (net (code "10") (name "Net-(IC1E-DIGPRPOC)") (class "Default")
      (node (ref "C119") (pin "1") (pinfunction "1_1") (pintype "passive"))
      (node (ref "C120") (pin "1") (pinfunction "1_1") (pintype "passive"))
      (node (ref "IC1") (pin "W31") (pinfunction "DIGPRPOC_W31") (pintype "power_in"))
      (node (ref "R84") (pin "2") (pinfunction "2_2") (pintype "passive"))
    )
    (net (code "11") (name "Net-(IC1E-VDD18_BIAS)") (class "Default")
      (node (ref "C132") (pin "1") (pinfunction "1_1") (pintype "passive"))
      (node (ref "FR29") (pin "1") (pinfunction "1_1") (pintype "passive"))
      (node (ref "IC1") (pin "E17") (pinfunction "VDD18_BIAS_E17") (pintype "power_in"))
    )
    (net (code "12") (name "Net-(IC1E-VDD18_DIG)") (class "Default")
      (node (ref "C117") (pin "1") (pinfunction "1_1") (pintype "passive"))
      (node (ref "IC1") (pin "D24") (pinfunction "VDD18_DIG_D24") (pintype "power_in"))
      (node (ref "R79") (pin "1") (pinfunction "1_1") (pintype "passive"))
    )
    (net (code "13") (name "Net-(IC1E-VDD18_LDO_RX)") (class "Default")
      (node (ref "C135") (pin "1") (pinfunction "1_1") (pintype "passive"))
      (node (ref "FR26") (pin "2") (pinfunction "2_2") (pintype "passive"))
      (node (ref "IC1") (pin "AE3") (pinfunction "VDD18_TIA_RFE_AE3") (pintype "power_in"))
      (node (ref "IC1") (pin "AF4") (pinfunction "VDD18_LDO_RX_AF4") (pintype "power_in"))
    )
    (net (code "14") (name "Net-(IC1E-VDD18_LDO_TX)") (class "Default")
      (node (ref "C136") (pin "1") (pinfunction "1_1") (pintype "passive"))
      (node (ref "FR25") (pin "2") (pinfunction "2_2") (pintype "passive"))
      (node (ref "IC1") (pin "N1") (pinfunction "VDD18_LDO_TX_N1") (pintype "power_in"))
    )
    (net (code "15") (name "Net-(IC1E-VDD18_RXBUF)") (class "Default")
      (node (ref "C137") (pin "1") (pinfunction "1_1") (pintype "passive"))
      (node (ref "FR33") (pin "1") (pinfunction "1_1") (pintype "passive"))
      (node (ref "IC1") (pin "AM26") (pinfunction "VDD18_RXBUF_AM26") (pintype "power_in"))
    )
    (net (code "16") (name "Net-(IC1E-VDD18_SXR)") (class "Default")
      (node (ref "C134") (pin "1") (pinfunction "1_1") (pintype "passive"))
      (node (ref "FR27") (pin "1") (pinfunction "1_1") (pintype "passive"))
      (node (ref "IC1") (pin "AM18") (pinfunction "VDD18_SXR_AM18") (pintype "power_in"))
    )
    (net (code "17") (name "Net-(IC1E-VDD18_TRF)") (class "Default")
      (node (ref "C131") (pin "1") (pinfunction "1_1") (pintype "passive"))
      (node (ref "FR30") (pin "1") (pinfunction "1_1") (pintype "passive"))
      (node (ref "IC1") (pin "D16") (pinfunction "VDD18_TRF_D16") (pintype "power_in"))
    )
    (net (code "18") (name "Net-(IC1E-VDD18_TXBUF)") (class "Default")
      (node (ref "C138") (pin "1") (pinfunction "1_1") (pintype "passive"))
      (node (ref "FR32") (pin "2") (pinfunction "2_2") (pintype "passive"))
      (node (ref "IC1") (pin "H6") (pinfunction "VDD18_TXBUF_H6") (pintype "power_in"))
    )
    (net (code "19") (name "Net-(IC1E-VDD18_VCO_CGEN)") (class "Default")
      (node (ref "C130") (pin "1") (pinfunction "1_1") (pintype "passive"))
      (node (ref "FR31") (pin "1") (pinfunction "1_1") (pintype "passive"))
      (node (ref "IC1") (pin "E21") (pinfunction "VDD18_VCO_CGEN_E21") (pintype "power_in"))
    )
    (net (code "20") (name "Net-(IC1E-VDD18_VCO_SXR)") (class "Default")
      (node (ref "C133") (pin "1") (pinfunction "1_1") (pintype "passive"))
      (node (ref "FR28") (pin "1") (pinfunction "1_1") (pintype "passive"))
      (node (ref "IC1") (pin "AK22") (pinfunction "VDD18_VCO_SXR_AK22") (pintype "power_in"))
    )
    (net (code "21") (name "Net-(IC1E-VDD18_VCO_SXT)") (class "Default")
      (node (ref "C129") (pin "1") (pinfunction "1_1") (pintype "passive"))
      (node (ref "FR24") (pin "1") (pinfunction "1_1") (pintype "passive"))
      (node (ref "IC1") (pin "G3") (pinfunction "VDD18_VCO_SXT_G3") (pintype "power_in"))
    )
    (net (code "22") (name "Net-(IC1F-DVDD_CGEN)") (class "Default")
      (node (ref "C84") (pin "1") (pinfunction "1_1") (pintype "passive"))
      (node (ref "C85") (pin "1") (pinfunction "1_1") (pintype "passive"))
      (node (ref "C86") (pin "1") (pinfunction "1_1") (pintype "passive"))
      (node (ref "FR3") (pin "1") (pinfunction "1_1") (pintype "passive"))
      (node (ref "IC1") (pin "A17") (pinfunction "DVDD_CGEN_A17") (pintype "power_in"))
      (node (ref "IC1") (pin "C25") (pinfunction "VDD12_DIG_C25") (pintype "power_in"))
      (node (ref "IC1") (pin "F24") (pinfunction "VDD_SPI_BUF_F24") (pintype "power_in"))
    )
    (net (code "23") (name "Net-(IC1F-DVDD_SXR)") (class "Default")
      (node (ref "C88") (pin "1") (pinfunction "1_1") (pintype "passive"))
      (node (ref "FR1") (pin "1") (pinfunction "1_1") (pintype "passive"))
      (node (ref "IC1") (pin "AL21") (pinfunction "DVDD_SXR_AL21") (pintype "power_in"))
    )
    (net (code "24") (name "Net-(IC1F-DVDD_SXT)") (class "Default")
      (node (ref "C87") (pin "2") (pinfunction "2_2") (pintype "passive"))
      (node (ref "FR2") (pin "1") (pinfunction "1_1") (pintype "passive"))
      (node (ref "IC1") (pin "M4") (pinfunction "DVDD_SXT_M4") (pintype "power_in"))
    )
    (net (code "25") (name "Net-(IC1F-VDD12O_VCO_SXT)") (class "Default")
      (node (ref "C109") (pin "2") (pinfunction "2_2") (pintype "passive"))
      (node (ref "FR4") (pin "1") (pinfunction "1_1") (pintype "passive"))
      (node (ref "IC1") (pin "J5") (pinfunction "VDD12O_VCO_SXT_J5") (pintype "power_in"))
      (node (ref "IC1") (pin "K6") (pinfunction "VDD12_VCO_SXT_K6") (pintype "power_in"))
    )
    (net (code "26") (name "Net-(IC1F-VDD12_LNA_RFE)") (class "Default")
      (node (ref "C106") (pin "1") (pinfunction "1_1") (pintype "passive"))
      (node (ref "FR8") (pin "1") (pinfunction "1_1") (pintype "passive"))
      (node (ref "IC1") (pin "AG5") (pinfunction "VDD12_LNA_RFE_AG5") (pintype "power_in"))
    )
    (net (code "27") (name "Net-(IC1F-VDD12_RXBUF)") (class "Default")
      (node (ref "C102") (pin "1") (pinfunction "1_1") (pintype "passive"))
      (node (ref "IC1") (pin "AP26") (pinfunction "VDD12_RXBUF_AP26") (pintype "power_in"))
      (node (ref "R78") (pin "1") (pinfunction "1_1") (pintype "passive"))
    )
    (net (code "28") (name "Net-(IC1F-VDD12_TIA_RFE)") (class "Default")
      (node (ref "C107") (pin "2") (pinfunction "2_2") (pintype "passive"))
      (node (ref "FR7") (pin "1") (pinfunction "1_1") (pintype "passive"))
      (node (ref "IC1") (pin "AD6") (pinfunction "VDD12_TIA_RFE_AD6") (pintype "power_in"))
    )
    (net (code "29") (name "Net-(IC1F-VDD12_TXBUF)") (class "Default")
      (node (ref "C95") (pin "1") (pinfunction "1_1") (pintype "passive"))
      (node (ref "IC1") (pin "G5") (pinfunction "VDD12_TXBUF_G5") (pintype "power_in"))
      (node (ref "R77") (pin "1") (pinfunction "1_1") (pintype "passive"))
    )
    (net (code "30") (name "Net-(IC1F-VDD12_VCO_SXR)") (class "Default")
      (node (ref "C103") (pin "1") (pinfunction "1_1") (pintype "passive"))
      (node (ref "FR11") (pin "1") (pinfunction "1_1") (pintype "passive"))
      (node (ref "IC1") (pin "AN23") (pinfunction "VDD12_VCO_SXR_AN23") (pintype "power_in"))
    )
    (net (code "31") (name "Net-(IC1F-VDD14_LNA_RFE)") (class "Default")
      (node (ref "C113") (pin "1") (pinfunction "1_1") (pintype "passive"))
      (node (ref "FR22") (pin "1") (pinfunction "1_1") (pintype "passive"))
      (node (ref "IC1") (pin "AF6") (pinfunction "VDD14_LNA_RFE_AF6") (pintype "power_in"))
    )
    (net (code "32") (name "Net-(IC1F-VDD14_RBB)") (class "Default")
      (node (ref "C115") (pin "1") (pinfunction "1_1") (pintype "passive"))
      (node (ref "FR20") (pin "1") (pinfunction "1_1") (pintype "passive"))
      (node (ref "IC1") (pin "AD4") (pinfunction "VDD14_RBB_AD4") (pintype "power_in"))
    )
    (net (code "33") (name "Net-(IC1F-VDD14_TIA_RFE)") (class "Default")
      (node (ref "C114") (pin "1") (pinfunction "1_1") (pintype "passive"))
      (node (ref "FR21") (pin "1") (pinfunction "1_1") (pintype "passive"))
      (node (ref "IC1") (pin "AF2") (pinfunction "VDD14_TIA_RFE_AF2") (pintype "power_in"))
    )
    (net (code "34") (name "Net-(IC1F-VDD14_VCO_CGEN)") (class "Default")
      (node (ref "C112") (pin "1") (pinfunction "1_1") (pintype "passive"))
      (node (ref "FR23") (pin "1") (pinfunction "1_1") (pintype "passive"))
      (node (ref "IC1") (pin "C21") (pinfunction "VDD14_VCO_CGEN_C21") (pintype "power_in"))
    )
    (net (code "35") (name "Net-(IC1F-VDDO_DIV_SXT)") (class "Default")
      (node (ref "C111") (pin "1") (pinfunction "1_1") (pintype "passive"))
      (node (ref "FR18") (pin "1") (pinfunction "1_1") (pintype "passive"))
      (node (ref "IC1") (pin "K2") (pinfunction "VDDO_DIV_SXT_K2") (pintype "power_in"))
      (node (ref "IC1") (pin "L5") (pinfunction "VDD_DIV_SXT_L5") (pintype "power_in"))
    )
    (net (code "36") (name "Net-(IC1F-VDDO_TLOBUF_TRF)") (class "Default")
      (node (ref "C97") (pin "1") (pinfunction "1_1") (pintype "passive"))
      (node (ref "FR17") (pin "1") (pinfunction "1_1") (pintype "passive"))
      (node (ref "IC1") (pin "D6") (pinfunction "VDDO_TLOBUF_TRF_D6") (pintype "power_in"))
      (node (ref "IC1") (pin "F8") (pinfunction "VDD_TLOBUF_TRF_F8") (pintype "power_in"))
    )
    (net (code "37") (name "Net-(IC1F-VDD_AFE)") (class "Default")
      (node (ref "C101") (pin "1") (pinfunction "1_1") (pintype "passive"))
      (node (ref "FR13") (pin "1") (pinfunction "1_1") (pintype "passive"))
      (node (ref "IC1") (pin "AJ25") (pinfunction "VDD_AFE_AJ25") (pintype "power_in"))
    )
    (net (code "38") (name "Net-(IC1F-VDD_CP_CGEN)") (class "Default")
      (node (ref "C100") (pin "2") (pinfunction "2_2") (pintype "passive"))
      (node (ref "FR14") (pin "1") (pinfunction "1_1") (pintype "passive"))
      (node (ref "IC1") (pin "F20") (pinfunction "VDD_CP_CGEN_F20") (pintype "power_in"))
    )
    (net (code "39") (name "Net-(IC1F-VDD_CP_SXR)") (class "Default")
      (node (ref "C105") (pin "1") (pinfunction "1_1") (pintype "passive"))
      (node (ref "FR9") (pin "1") (pinfunction "1_1") (pintype "passive"))
      (node (ref "IC1") (pin "AL19") (pinfunction "VDD_CP_SXR_AL19") (pintype "power_in"))
    )
    (net (code "40") (name "Net-(IC1F-VDD_CP_SXT)") (class "Default")
      (node (ref "C108") (pin "1") (pinfunction "1_1") (pintype "passive"))
      (node (ref "FR5") (pin "1") (pinfunction "1_1") (pintype "passive"))
      (node (ref "IC1") (pin "J3") (pinfunction "VDD_CP_SXT_J3") (pintype "power_in"))
    )
    (net (code "41") (name "Net-(IC1F-VDD_DIV_CGEN)") (class "Default")
      (node (ref "C99") (pin "1") (pinfunction "1_1") (pintype "passive"))
      (node (ref "FR15") (pin "1") (pinfunction "1_1") (pintype "passive"))
      (node (ref "IC1") (pin "E19") (pinfunction "VDD_DIV_CGEN_E19") (pintype "power_in"))
    )
    (net (code "42") (name "Net-(IC1F-VDD_DIV_SXR)") (class "Default")
      (node (ref "C104") (pin "1") (pinfunction "1_1") (pintype "passive"))
      (node (ref "FR10") (pin "1") (pinfunction "1_1") (pintype "passive"))
      (node (ref "IC1") (pin "AM20") (pinfunction "VDD_DIV_SXR_AM20") (pintype "power_in"))
    )
    (net (code "43") (name "Net-(IC1F-VDD_MXLOBUF_RFE)") (class "Default")
      (node (ref "C116") (pin "1") (pinfunction "1_1") (pintype "passive"))
      (node (ref "FR19") (pin "1") (pinfunction "1_1") (pintype "passive"))
      (node (ref "IC1") (pin "AN17") (pinfunction "VDD_MXLOBUF_RFE_AN17") (pintype "power_in"))
    )
    (net (code "44") (name "Net-(IC1F-VDD_TBB)") (class "Default")
      (node (ref "C96") (pin "1") (pinfunction "1_1") (pintype "passive"))
      (node (ref "FR6") (pin "1") (pinfunction "1_1") (pintype "passive"))
      (node (ref "IC1") (pin "P4") (pinfunction "VDD_TBB_P4") (pintype "power_in"))
    )
    (net (code "45") (name "Net-(IC1F-VDD_TPAD_TRF)") (class "Default")
      (node (ref "C98") (pin "1") (pinfunction "1_1") (pintype "passive"))
      (node (ref "FR16") (pin "1") (pinfunction "1_1") (pintype "passive"))
      (node (ref "IC1") (pin "B16") (pinfunction "VDD_TPAD_TRF_B16") (pintype "power_in"))
    )
    (net (code "46") (name "VCC1P4_LMS1") (class "Default")
      (node (ref "FR18") (pin "2") (pinfunction "2_2") (pintype "passive"))
      (node (ref "FR19") (pin "2") (pinfunction "2_2") (pintype "passive"))
      (node (ref "FR20") (pin "2") (pinfunction "2_2") (pintype "passive"))
      (node (ref "FR21") (pin "2") (pinfunction "2_2") (pintype "passive"))
      (node (ref "FR22") (pin "2") (pinfunction "2_2") (pintype "passive"))
      (node (ref "FR23") (pin "2") (pinfunction "2_2") (pintype "passive"))
      (node (ref "R75") (pin "1") (pinfunction "1_1") (pintype "passive"))
    )
    (net (code "47") (name "VCC1P8_LMS1") (class "Default")
      (node (ref "FR24") (pin "2") (pinfunction "2_2") (pintype "passive"))
      (node (ref "FR25") (pin "1") (pinfunction "1_1") (pintype "passive"))
      (node (ref "FR26") (pin "1") (pinfunction "1_1") (pintype "passive"))
      (node (ref "FR27") (pin "2") (pinfunction "2_2") (pintype "passive"))
      (node (ref "FR28") (pin "2") (pinfunction "2_2") (pintype "passive"))
      (node (ref "FR29") (pin "2") (pinfunction "2_2") (pintype "passive"))
      (node (ref "FR30") (pin "2") (pinfunction "2_2") (pintype "passive"))
      (node (ref "FR31") (pin "2") (pinfunction "2_2") (pintype "passive"))
      (node (ref "R79") (pin "2") (pinfunction "2_2") (pintype "passive"))
      (node (ref "R85") (pin "2") (pinfunction "2_2") (pintype "passive"))
      (node (ref "R86") (pin "1") (pinfunction "1_1") (pintype "passive"))
    )
    (net (code "48") (name "VCC1P25_LMS1") (class "Default")
      (node (ref "FR1") (pin "2") (pinfunction "2_2") (pintype "passive"))
      (node (ref "FR10") (pin "2") (pinfunction "2_2") (pintype "passive"))
      (node (ref "FR11") (pin "2") (pinfunction "2_2") (pintype "passive"))
      (node (ref "FR12") (pin "2") (pinfunction "2_2") (pintype "passive"))
      (node (ref "FR13") (pin "2") (pinfunction "2_2") (pintype "passive"))
      (node (ref "FR14") (pin "2") (pinfunction "2_2") (pintype "passive"))
      (node (ref "FR15") (pin "2") (pinfunction "2_2") (pintype "passive"))
      (node (ref "FR16") (pin "2") (pinfunction "2_2") (pintype "passive"))
      (node (ref "FR17") (pin "2") (pinfunction "2_2") (pintype "passive"))
      (node (ref "FR2") (pin "2") (pinfunction "2_2") (pintype "passive"))
      (node (ref "FR3") (pin "2") (pinfunction "2_2") (pintype "passive"))
      (node (ref "FR4") (pin "2") (pinfunction "2_2") (pintype "passive"))
      (node (ref "FR5") (pin "2") (pinfunction "2_2") (pintype "passive"))
      (node (ref "FR6") (pin "2") (pinfunction "2_2") (pintype "passive"))
      (node (ref "FR7") (pin "2") (pinfunction "2_2") (pintype "passive"))
      (node (ref "FR8") (pin "2") (pinfunction "2_2") (pintype "passive"))
      (node (ref "FR9") (pin "2") (pinfunction "2_2") (pintype "passive"))
      (node (ref "R76") (pin "1") (pinfunction "1_1") (pintype "passive"))
    )
    (net (code "49") (name "VDIO_LMS") (class "Default")
      (node (ref "C118") (pin "2") (pinfunction "2_2") (pintype "passive"))
      (node (ref "R80") (pin "1") (pinfunction "1_1") (pintype "passive"))
      (node (ref "R81") (pin "1") (pinfunction "1_1") (pintype "passive"))
      (node (ref "R82") (pin "1") (pinfunction "1_1") (pintype "passive"))
      (node (ref "R83") (pin "1") (pinfunction "1_1") (pintype "passive"))
      (node (ref "R84") (pin "1") (pinfunction "1_1") (pintype "passive"))
    )
  )
)
